# POWER_GEN.net
KiCad netlist of a schematic drawn in Altium Designer
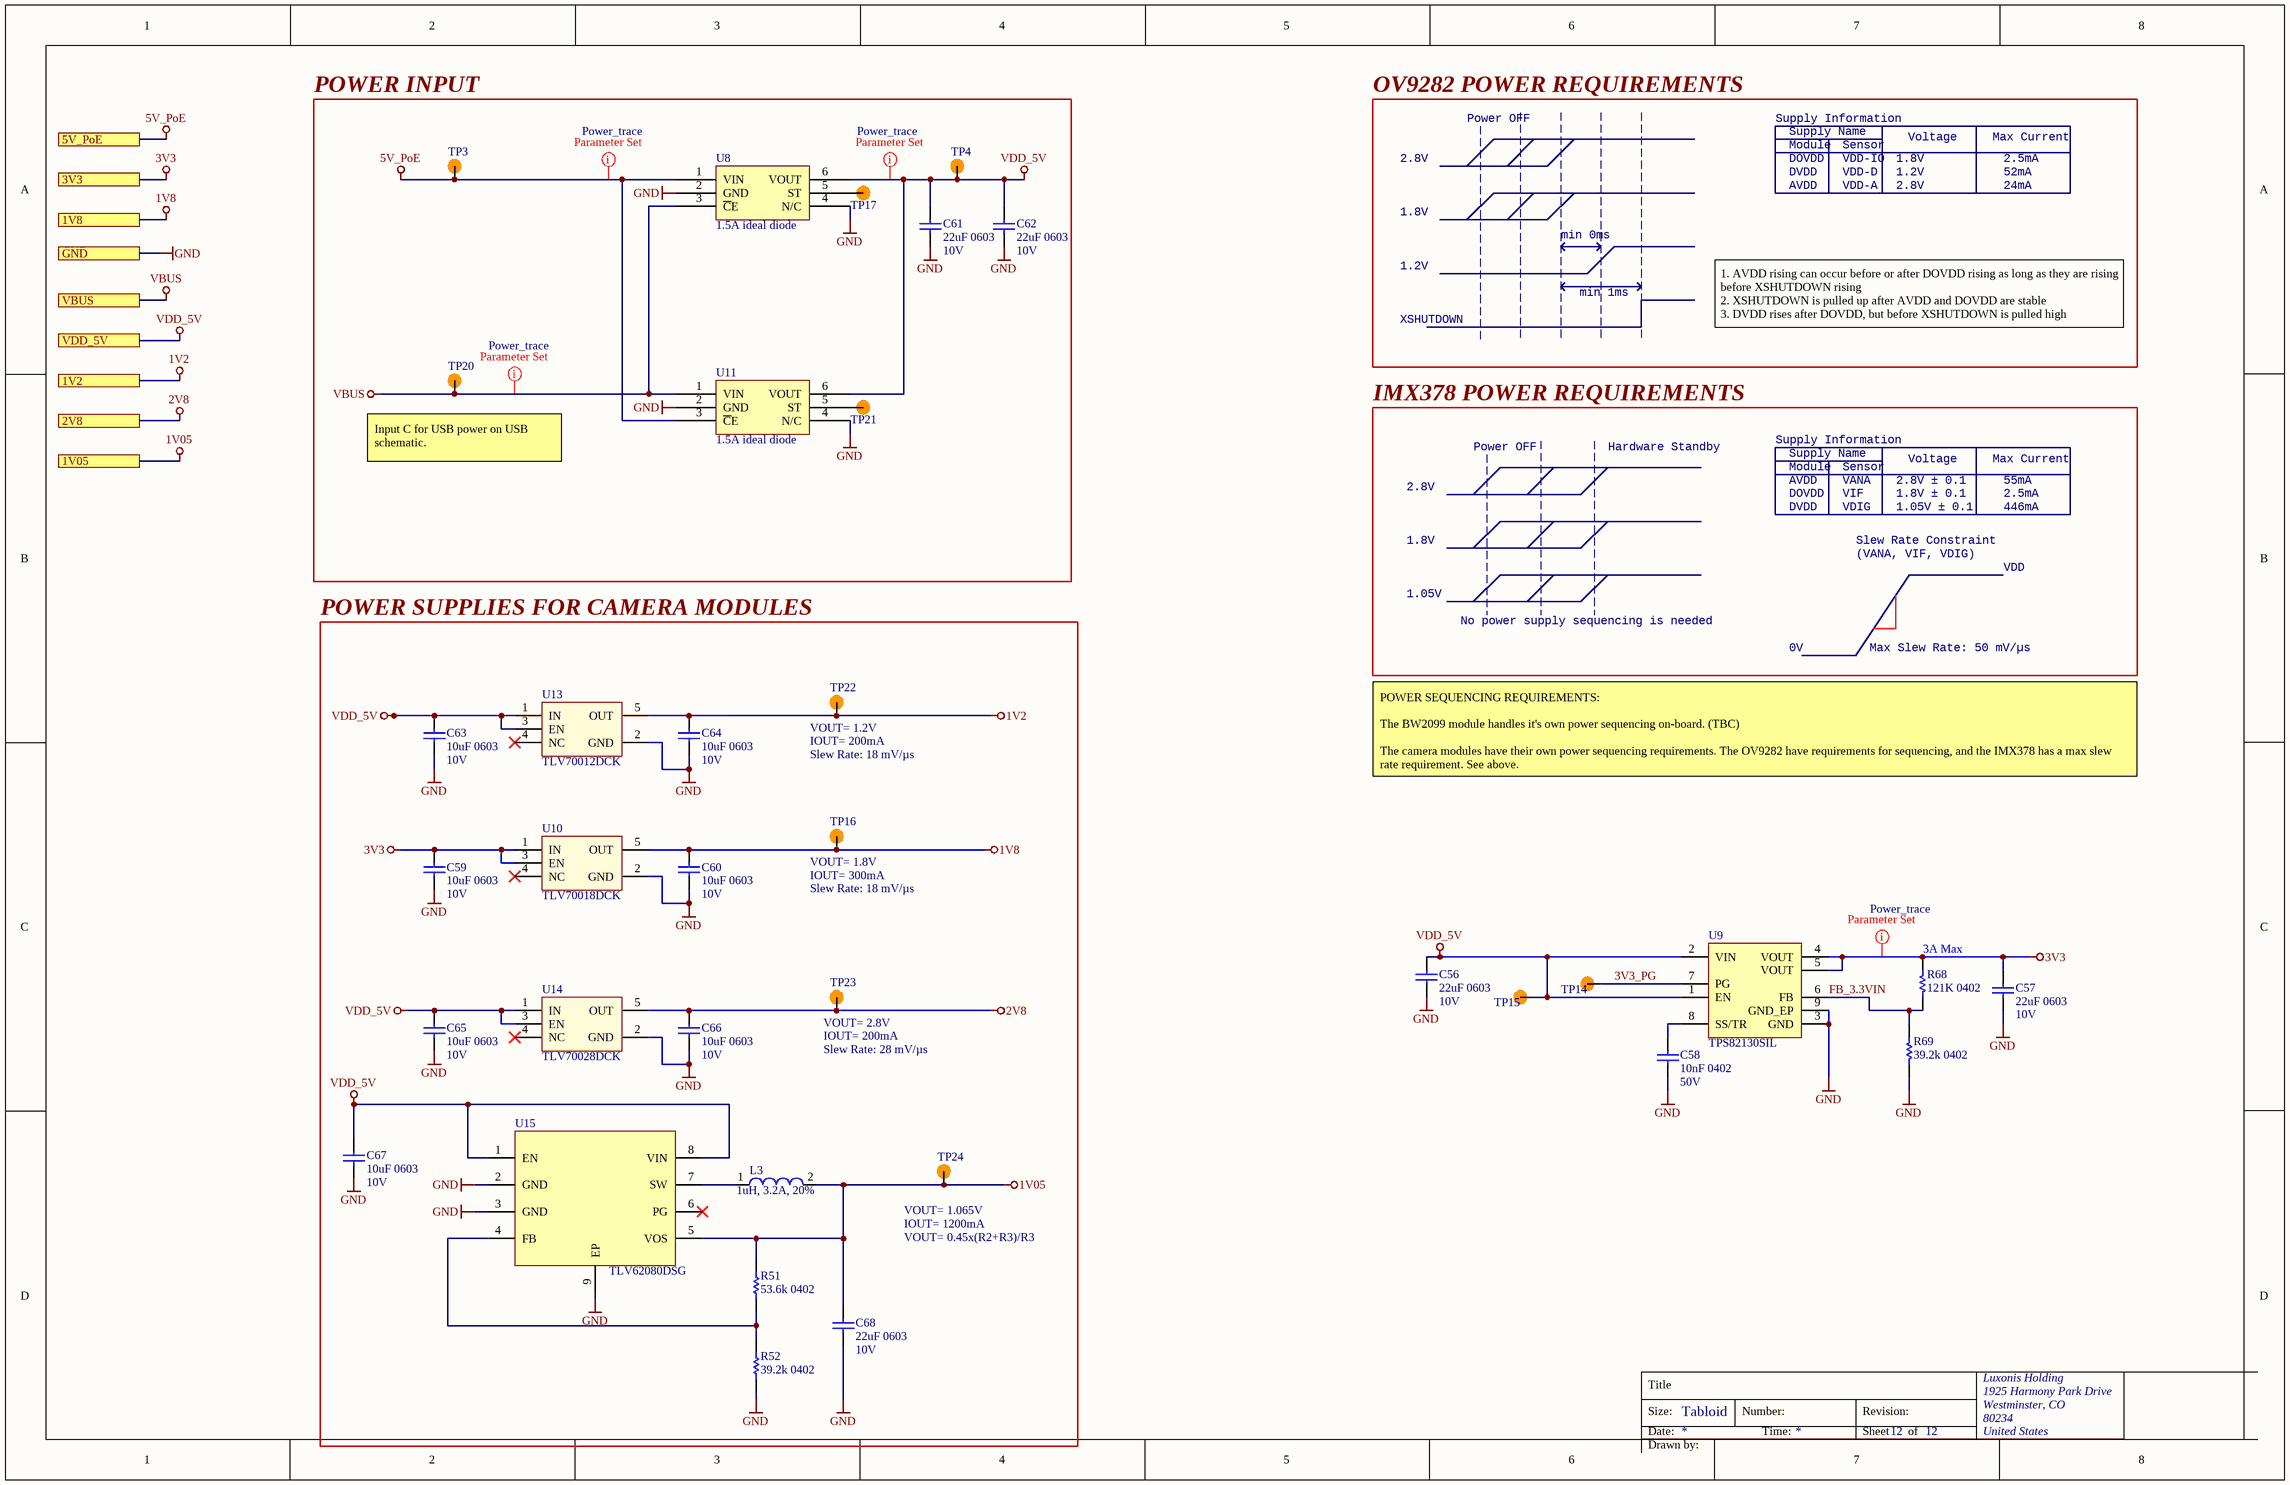
[diagram p0: POWER_GEN.SchDoc]

(export (version "E")
  (design (tool "Eeschema 10.0.6"))
  (components
    (comp (ref "C56")
      (value "22uF 0603")
      (footprint "CAP_Altium_Vault_Generic:CAPC0603(1608)100_N")
      (description "CAP CER 22UF 10V X5R 0603 20%")
      (fields (field (name "TOLERANCE") "20%") (field (name "VOLTAGE RATING") "10V"))
      (libsource (lib "LuxonisMaster") (part "GRM188R61A226ME15D"))
    )
    (comp (ref "C57")
      (value "22uF 0603")
      (footprint "CAP_Altium_Vault_Generic:CAPC0603(1608)100_N")
      (description "CAP CER 22UF 10V X5R 0603 20%")
      (fields (field (name "TOLERANCE") "20%") (field (name "VOLTAGE RATING") "10V"))
      (libsource (lib "LuxonisMaster") (part "GRM188R61A226ME15D"))
    )
    (comp (ref "C58")
      (value "10nF 0402")
      (footprint "CAP_Altium_Vault_Generic:CAPC0402(1005)60_N")
      (description "CAP CER 10000PF 50V X7R 0402")
      (fields
        (field (name "TOLERANCE") "10%")
        (field (name "VOLTAGE") "25V")
        (field (name "VOLTAGE RATING") "50V")
      )
      (libsource (lib "LuxonisMaster") (part "GRM155R71H103KA88D"))
    )
    (comp (ref "C59")
      (value "10uF 0603")
      (footprint "CAP_Altium_Vault_Generic:CAPC0603(1608)100_N")
      (description "CAP CER 10UF 10V X5R 0603 20%")
      (fields (field (name "TOLERANCE") "20%") (field (name "VOLTAGE RATING") "10V"))
      (libsource (lib "LuxonisMaster") (part "GRM188R61A106ME69D"))
    )
    (comp (ref "C60")
      (value "10uF 0603")
      (footprint "CAP_Altium_Vault_Generic:CAPC0603(1608)100_N")
      (description "CAP CER 10UF 10V X5R 0603 20%")
      (fields (field (name "TOLERANCE") "20%") (field (name "VOLTAGE RATING") "10V"))
      (libsource (lib "LuxonisMaster") (part "GRM188R61A106ME69D"))
    )
    (comp (ref "C61")
      (value "22uF 0603")
      (footprint "CAP_Altium_Vault_Generic:CAPC0603(1608)100_L")
      (description "CAP CER 22UF 10V X5R 0603 20%")
      (fields (field (name "TOLERANCE") "20%") (field (name "VOLTAGE RATING") "10V"))
      (libsource (lib "LuxonisMaster") (part "GRM188R61A226ME15D"))
    )
    (comp (ref "C62")
      (value "22uF 0603")
      (footprint "CAP_Altium_Vault_Generic:CAPC0603(1608)100_L")
      (description "CAP CER 22UF 10V X5R 0603 20%")
      (fields (field (name "TOLERANCE") "20%") (field (name "VOLTAGE RATING") "10V"))
      (libsource (lib "LuxonisMaster") (part "GRM188R61A226ME15D"))
    )
    (comp (ref "C63")
      (value "10uF 0603")
      (footprint "CAP_Altium_Vault_Generic:CAPC0603(1608)100_L")
      (description "CAP CER 10UF 10V X5R 0603 20%")
      (fields (field (name "TOLERANCE") "20%") (field (name "VOLTAGE RATING") "10V"))
      (libsource (lib "LuxonisMaster") (part "GRM188R61A106ME69D"))
    )
    (comp (ref "C64")
      (value "10uF 0603")
      (footprint "CAP_Altium_Vault_Generic:CAPC0603(1608)100_L")
      (description "CAP CER 10UF 10V X5R 0603 20%")
      (fields (field (name "TOLERANCE") "20%") (field (name "VOLTAGE RATING") "10V"))
      (libsource (lib "LuxonisMaster") (part "GRM188R61A106ME69D"))
    )
    (comp (ref "C65")
      (value "10uF 0603")
      (footprint "CAP_Altium_Vault_Generic:CAPC0603(1608)100_L")
      (description "CAP CER 10UF 10V X5R 0603 20%")
      (fields (field (name "TOLERANCE") "20%") (field (name "VOLTAGE RATING") "10V"))
      (libsource (lib "LuxonisMaster") (part "GRM188R61A106ME69D"))
    )
    (comp (ref "C66")
      (value "10uF 0603")
      (footprint "CAP_Altium_Vault_Generic:CAPC0603(1608)100_L")
      (description "CAP CER 10UF 10V X5R 0603 20%")
      (fields (field (name "TOLERANCE") "20%") (field (name "VOLTAGE RATING") "10V"))
      (libsource (lib "LuxonisMaster") (part "GRM188R61A106ME69D"))
    )
    (comp (ref "C67")
      (value "10uF 0603")
      (footprint "CAP_Altium_Vault_Generic:CAPC0603(1608)100_L")
      (description "CAP CER 10UF 10V X5R 0603 20%")
      (fields (field (name "TOLERANCE") "20%") (field (name "VOLTAGE RATING") "10V"))
      (libsource (lib "LuxonisMaster") (part "GRM188R61A106ME69D"))
    )
    (comp (ref "C68")
      (value "22uF 0603")
      (footprint "CAP_Altium_Vault_Generic:CAPC0603(1608)100_L")
      (description "CAP CER 22UF 10V X5R 0603 20%")
      (fields (field (name "TOLERANCE") "20%") (field (name "VOLTAGE RATING") "10V"))
      (libsource (lib "LuxonisMaster") (part "GRM188R61A226ME15D"))
    )
    (comp (ref "L3")
      (value "1uH, 3.2A, 20%")
      (footprint "LuxonisMaster:DFE252012P-1R0M=P2")
      (description "FIXED IND 1UH 3.2A 42 MOHM SMD")
      (fields
        (field (name "MANUFACTURER") "Murata")
        (field (name "MANUFACTURER PART NUMBER") "DFE252012P-1R0M=P2")
      )
      (libsource (lib "LuxonisMaster") (part "DFE252012P-1R0M=P2"))
    )
    (comp (ref "R51")
      (value "53.6k 0402")
      (footprint "RES_Altium_Vault_Generic:RESC0402(1005)_L")
      (description "RES SMD 53.6K OHM 1% 1/16W 0402")
      (fields (field (name "TOLERANCE") "1%"))
      (libsource (lib "LuxonisMaster") (part "CRCW040253K6FKED"))
    )
    (comp (ref "R52")
      (value "39.2k 0402")
      (footprint "RES_Altium_Vault_Generic:RESC0402(1005)_L")
      (description "RES SMD 39.2K OHM 1% 1/16W 0402")
      (fields (field (name "TOLERANCE") "1%"))
      (libsource (lib "LuxonisMaster") (part "CRCW040239K2FKED"))
    )
    (comp (ref "R68")
      (value "121K 0402")
      (footprint "RES_Altium_Vault_Generic:RESC0402(1005)_N")
      (description "RES SMD 121K OHM 1% 1/16W 0402")
      (fields (field (name "TOLERANCE") "1%"))
      (libsource (lib "LuxonisMaster") (part "RC0402FR-07121KL"))
    )
    (comp (ref "R69")
      (value "39.2k 0402")
      (footprint "RES_Altium_Vault_Generic:RESC0402(1005)_N")
      (description "RES SMD 39.2K OHM 1% 1/16W 0402")
      (fields (field (name "TOLERANCE") "1%"))
      (libsource (lib "LuxonisMaster") (part "CRCW040239K2FKED"))
    )
    (comp (ref "TP3")
      (value "TP100_200_NS")
      (footprint "LuxonisMaster:TP100_200_NS")
      (libsource (lib "LuxonisMaster") (part "TEST_POINT"))
    )
    (comp (ref "TP4")
      (value "TP100_200_NS")
      (footprint "LuxonisMaster:TP100_200_NS")
      (libsource (lib "LuxonisMaster") (part "TEST_POINT"))
    )
    (comp (ref "TP14")
      (value "TP100_200_NS")
      (footprint "LuxonisMaster:TP100_200_NS")
      (libsource (lib "LuxonisMaster") (part "TEST_POINT"))
    )
    (comp (ref "TP15")
      (value "TP100_200_NS")
      (footprint "LuxonisMaster:TP100_200_NS")
      (libsource (lib "LuxonisMaster") (part "TEST_POINT"))
    )
    (comp (ref "TP16")
      (value "TP100_200_NS")
      (footprint "LuxonisMaster:TP100_200_NS")
      (libsource (lib "LuxonisMaster") (part "TEST_POINT"))
    )
    (comp (ref "TP17")
      (value "TP100_200_NS")
      (footprint "LuxonisMaster:TP100_200_NS")
      (libsource (lib "LuxonisMaster") (part "TEST_POINT"))
    )
    (comp (ref "TP20")
      (value "TP100_200_NS")
      (footprint "LuxonisMaster:TP100_200_NS")
      (libsource (lib "LuxonisMaster") (part "TEST_POINT"))
    )
    (comp (ref "TP21")
      (value "TP100_200_NS")
      (footprint "LuxonisMaster:TP100_200_NS")
      (libsource (lib "LuxonisMaster") (part "TEST_POINT"))
    )
    (comp (ref "TP22")
      (value "TP100_200_NS")
      (footprint "LuxonisMaster:TP100_200_NS")
      (libsource (lib "LuxonisMaster") (part "TEST_POINT"))
    )
    (comp (ref "TP23")
      (value "TP100_200_NS")
      (footprint "LuxonisMaster:TP100_200_NS")
      (libsource (lib "LuxonisMaster") (part "TEST_POINT"))
    )
    (comp (ref "TP24")
      (value "TP100_200_NS")
      (footprint "LuxonisMaster:TP100_200_NS")
      (libsource (lib "LuxonisMaster") (part "TEST_POINT"))
    )
    (comp (ref "U8")
      (value "1.5A ideal diode")
      (footprint "LuxonisMaster:LM66100DCKR")
      (description "IC OR CTRLR IDEAL DIODE SC70-6")
      (libsource (lib "LuxonisMaster") (part "LM66100DCKR"))
    )
    (comp (ref "U9")
      (value "TPS82130SIL")
      (footprint "LuxonisMaster:TPS82130SIL")
      (description "DC DC CONVERTER 0.9-5V")
      (libsource (lib "LuxonisMaster") (part "TPS82130SIL"))
    )
    (comp (ref "U10")
      (value "TLV70018DCK")
      (footprint "LuxonisMaster:TLV70018DCK")
      (description "IC REG LINEAR 1.8V 200MA SC70-5 Linear Voltage Regulator IC  1 Output  200mA SC-70-5")
      (libsource (lib "LuxonisMaster") (part "TLV70018DCK"))
    )
    (comp (ref "U11")
      (value "1.5A ideal diode")
      (footprint "LuxonisMaster:LM66100DCKR")
      (description "IC OR CTRLR IDEAL DIODE SC70-6")
      (libsource (lib "LuxonisMaster") (part "LM66100DCKR"))
    )
    (comp (ref "U13")
      (value "TLV70012DCK")
      (footprint "LuxonisMaster:TLV70012DCK")
      (description "IC REG LINEAR 1.2V 200MA SC70-5")
      (libsource (lib "LuxonisMaster") (part "TLV70012DCK"))
    )
    (comp (ref "U14")
      (value "TLV70028DCK")
      (footprint "LuxonisMaster:TLV70028DCK")
      (description "IC REG LINEAR 2.8V 200MA SC70-5 Linear Voltage Regulator IC  1 Output  200mA SC-70-5")
      (libsource (lib "LuxonisMaster") (part "TLV70028DCK"))
    )
    (comp (ref "U15")
      (value "TLV62080DSG")
      (footprint "LuxonisMaster:TLV62080DSG")
      (description "IC REG BUCK ADJ 1.2A SYNC 8WSON")
      (libsource (lib "LuxonisMaster") (part "TLV62080DSG"))
    )
  )
  (nets
    (net (code "1") (name "/3V3_PG") (class "Default")
      (node (ref "TP14") (pin "1") (pintype "passive"))
      (node (ref "U9") (pin "7") (pinfunction "PG_7") (pintype "passive"))
    )
    (net (code "2") (name "/FB_3.3VIN") (class "Default")
      (node (ref "R68") (pin "2") (pinfunction "2_2") (pintype "passive"))
      (node (ref "R69") (pin "1") (pinfunction "1_1") (pintype "passive"))
      (node (ref "U9") (pin "6") (pinfunction "FB_6") (pintype "passive"))
    )
    (net (code "3") (name "1V2") (class "Default")
      (node (ref "C64") (pin "2") (pinfunction "2_2") (pintype "passive"))
      (node (ref "TP22") (pin "1") (pintype "passive"))
      (node (ref "U13") (pin "5") (pinfunction "OUT_5") (pintype "passive"))
    )
    (net (code "4") (name "1V05") (class "Default")
      (node (ref "C68") (pin "2") (pinfunction "2_2") (pintype "passive"))
      (node (ref "L3") (pin "2") (pinfunction "2_2") (pintype "passive"))
      (node (ref "R51") (pin "2") (pinfunction "2_2") (pintype "passive"))
      (node (ref "TP24") (pin "1") (pintype "passive"))
      (node (ref "U15") (pin "5") (pinfunction "VOS_5") (pintype "passive"))
    )
    (net (code "5") (name "1V8") (class "Default")
      (node (ref "C60") (pin "2") (pinfunction "2_2") (pintype "passive"))
      (node (ref "TP16") (pin "1") (pintype "passive"))
      (node (ref "U10") (pin "5") (pinfunction "OUT_5") (pintype "passive"))
    )
    (net (code "6") (name "2V8") (class "Default")
      (node (ref "C66") (pin "2") (pinfunction "2_2") (pintype "passive"))
      (node (ref "TP23") (pin "1") (pintype "passive"))
      (node (ref "U14") (pin "5") (pinfunction "OUT_5") (pintype "passive"))
    )
    (net (code "7") (name "3V3") (class "Default")
      (node (ref "C57") (pin "1") (pinfunction "1_1") (pintype "passive"))
      (node (ref "C59") (pin "2") (pinfunction "2_2") (pintype "passive"))
      (node (ref "R68") (pin "1") (pinfunction "1_1") (pintype "passive"))
      (node (ref "U10") (pin "1") (pinfunction "IN_1") (pintype "passive"))
      (node (ref "U10") (pin "3") (pinfunction "EN_3") (pintype "passive"))
      (node (ref "U9") (pin "4") (pinfunction "VOUT_4") (pintype "passive"))
      (node (ref "U9") (pin "5") (pinfunction "VOUT_5") (pintype "passive"))
    )
    (net (code "8") (name "5V_PoE") (class "Default")
      (node (ref "TP3") (pin "1") (pintype "passive"))
      (node (ref "U11") (pin "3") (pinfunction "~{C}E_3") (pintype "passive"))
      (node (ref "U8") (pin "1") (pinfunction "VIN_1") (pintype "passive"))
    )
    (net (code "9") (name "GND") (class "Default")
      (node (ref "C56") (pin "1") (pinfunction "1_1") (pintype "passive"))
      (node (ref "C57") (pin "2") (pinfunction "2_2") (pintype "passive"))
      (node (ref "C58") (pin "1") (pinfunction "1_1") (pintype "passive"))
      (node (ref "C59") (pin "1") (pinfunction "1_1") (pintype "passive"))
      (node (ref "C60") (pin "1") (pinfunction "1_1") (pintype "passive"))
      (node (ref "C61") (pin "1") (pinfunction "1_1") (pintype "passive"))
      (node (ref "C62") (pin "1") (pinfunction "1_1") (pintype "passive"))
      (node (ref "C63") (pin "1") (pinfunction "1_1") (pintype "passive"))
      (node (ref "C64") (pin "1") (pinfunction "1_1") (pintype "passive"))
      (node (ref "C65") (pin "1") (pinfunction "1_1") (pintype "passive"))
      (node (ref "C66") (pin "1") (pinfunction "1_1") (pintype "passive"))
      (node (ref "C67") (pin "1") (pinfunction "1_1") (pintype "passive"))
      (node (ref "C68") (pin "1") (pinfunction "1_1") (pintype "passive"))
      (node (ref "R52") (pin "1") (pinfunction "1_1") (pintype "passive"))
      (node (ref "R69") (pin "2") (pinfunction "2_2") (pintype "passive"))
      (node (ref "U10") (pin "2") (pinfunction "GND_2") (pintype "passive"))
      (node (ref "U11") (pin "2") (pinfunction "GND_2") (pintype "passive"))
      (node (ref "U11") (pin "4") (pinfunction "N/C_4") (pintype "passive"))
      (node (ref "U13") (pin "2") (pinfunction "GND_2") (pintype "passive"))
      (node (ref "U14") (pin "2") (pinfunction "GND_2") (pintype "passive"))
      (node (ref "U15") (pin "2") (pinfunction "GND_2") (pintype "passive"))
      (node (ref "U15") (pin "3") (pinfunction "GND_3") (pintype "passive"))
      (node (ref "U15") (pin "9") (pinfunction "EP_9") (pintype "passive"))
      (node (ref "U8") (pin "2") (pinfunction "GND_2") (pintype "passive"))
      (node (ref "U8") (pin "4") (pinfunction "N/C_4") (pintype "passive"))
      (node (ref "U9") (pin "3") (pinfunction "GND_3") (pintype "passive"))
      (node (ref "U9") (pin "9") (pinfunction "GND_EP_9") (pintype "passive"))
    )
    (net (code "10") (name "Net-(U8-ST)") (class "Default")
      (node (ref "TP17") (pin "1") (pintype "passive"))
      (node (ref "U8") (pin "5") (pinfunction "ST_5") (pintype "passive"))
    )
    (net (code "11") (name "Net-(U9-SS{slash}TR)") (class "Default")
      (node (ref "C58") (pin "2") (pinfunction "2_2") (pintype "passive"))
      (node (ref "U9") (pin "8") (pinfunction "SS/TR_8") (pintype "passive"))
    )
    (net (code "12") (name "Net-(U11-ST)") (class "Default")
      (node (ref "TP21") (pin "1") (pintype "passive"))
      (node (ref "U11") (pin "5") (pinfunction "ST_5") (pintype "passive"))
    )
    (net (code "13") (name "Net-(U15-FB)") (class "Default")
      (node (ref "R51") (pin "1") (pinfunction "1_1") (pintype "passive"))
      (node (ref "R52") (pin "2") (pinfunction "2_2") (pintype "passive"))
      (node (ref "U15") (pin "4") (pinfunction "FB_4") (pintype "passive"))
    )
    (net (code "14") (name "Net-(U15-SW)") (class "Default")
      (node (ref "L3") (pin "1") (pinfunction "1_1") (pintype "passive"))
      (node (ref "U15") (pin "7") (pinfunction "SW_7") (pintype "passive"))
    )
    (net (code "15") (name "VBUS") (class "Default")
      (node (ref "TP20") (pin "1") (pintype "passive"))
      (node (ref "U11") (pin "1") (pinfunction "VIN_1") (pintype "passive"))
      (node (ref "U8") (pin "3") (pinfunction "~{C}E_3") (pintype "passive"))
    )
    (net (code "16") (name "VDD_5V") (class "Default")
      (node (ref "C56") (pin "2") (pinfunction "2_2") (pintype "passive"))
      (node (ref "C61") (pin "2") (pinfunction "2_2") (pintype "passive"))
      (node (ref "C62") (pin "2") (pinfunction "2_2") (pintype "passive"))
      (node (ref "C63") (pin "2") (pinfunction "2_2") (pintype "passive"))
      (node (ref "C65") (pin "2") (pinfunction "2_2") (pintype "passive"))
      (node (ref "C67") (pin "2") (pinfunction "2_2") (pintype "passive"))
      (node (ref "TP15") (pin "1") (pintype "passive"))
      (node (ref "TP4") (pin "1") (pintype "passive"))
      (node (ref "U11") (pin "6") (pinfunction "VOUT_6") (pintype "passive"))
      (node (ref "U13") (pin "1") (pinfunction "IN_1") (pintype "passive"))
      (node (ref "U13") (pin "3") (pinfunction "EN_3") (pintype "passive"))
      (node (ref "U14") (pin "1") (pinfunction "IN_1") (pintype "passive"))
      (node (ref "U14") (pin "3") (pinfunction "EN_3") (pintype "passive"))
      (node (ref "U15") (pin "1") (pinfunction "EN_1") (pintype "passive"))
      (node (ref "U15") (pin "8") (pinfunction "VIN_8") (pintype "passive"))
      (node (ref "U8") (pin "6") (pinfunction "VOUT_6") (pintype "passive"))
      (node (ref "U9") (pin "1") (pinfunction "EN_1") (pintype "passive"))
      (node (ref "U9") (pin "2") (pinfunction "VIN_2") (pintype "passive"))
    )
    (net (code "17") (name "unconnected-(U10-NC-Pad4)") (class "Default")
      (node (ref "U10") (pin "4") (pinfunction "NC_4") (pintype "passive+no_connect"))
    )
    (net (code "18") (name "unconnected-(U13-NC-Pad4)") (class "Default")
      (node (ref "U13") (pin "4") (pinfunction "NC_4") (pintype "passive+no_connect"))
    )
    (net (code "19") (name "unconnected-(U14-NC-Pad4)") (class "Default")
      (node (ref "U14") (pin "4") (pinfunction "NC_4") (pintype "passive+no_connect"))
    )
    (net (code "20") (name "unconnected-(U15-PG-Pad6)") (class "Default")
      (node (ref "U15") (pin "6") (pinfunction "PG_6") (pintype "passive+no_connect"))
    )
  )
)
